# ME433.net
KiCad netlist of a schematic drawn in EAGLE
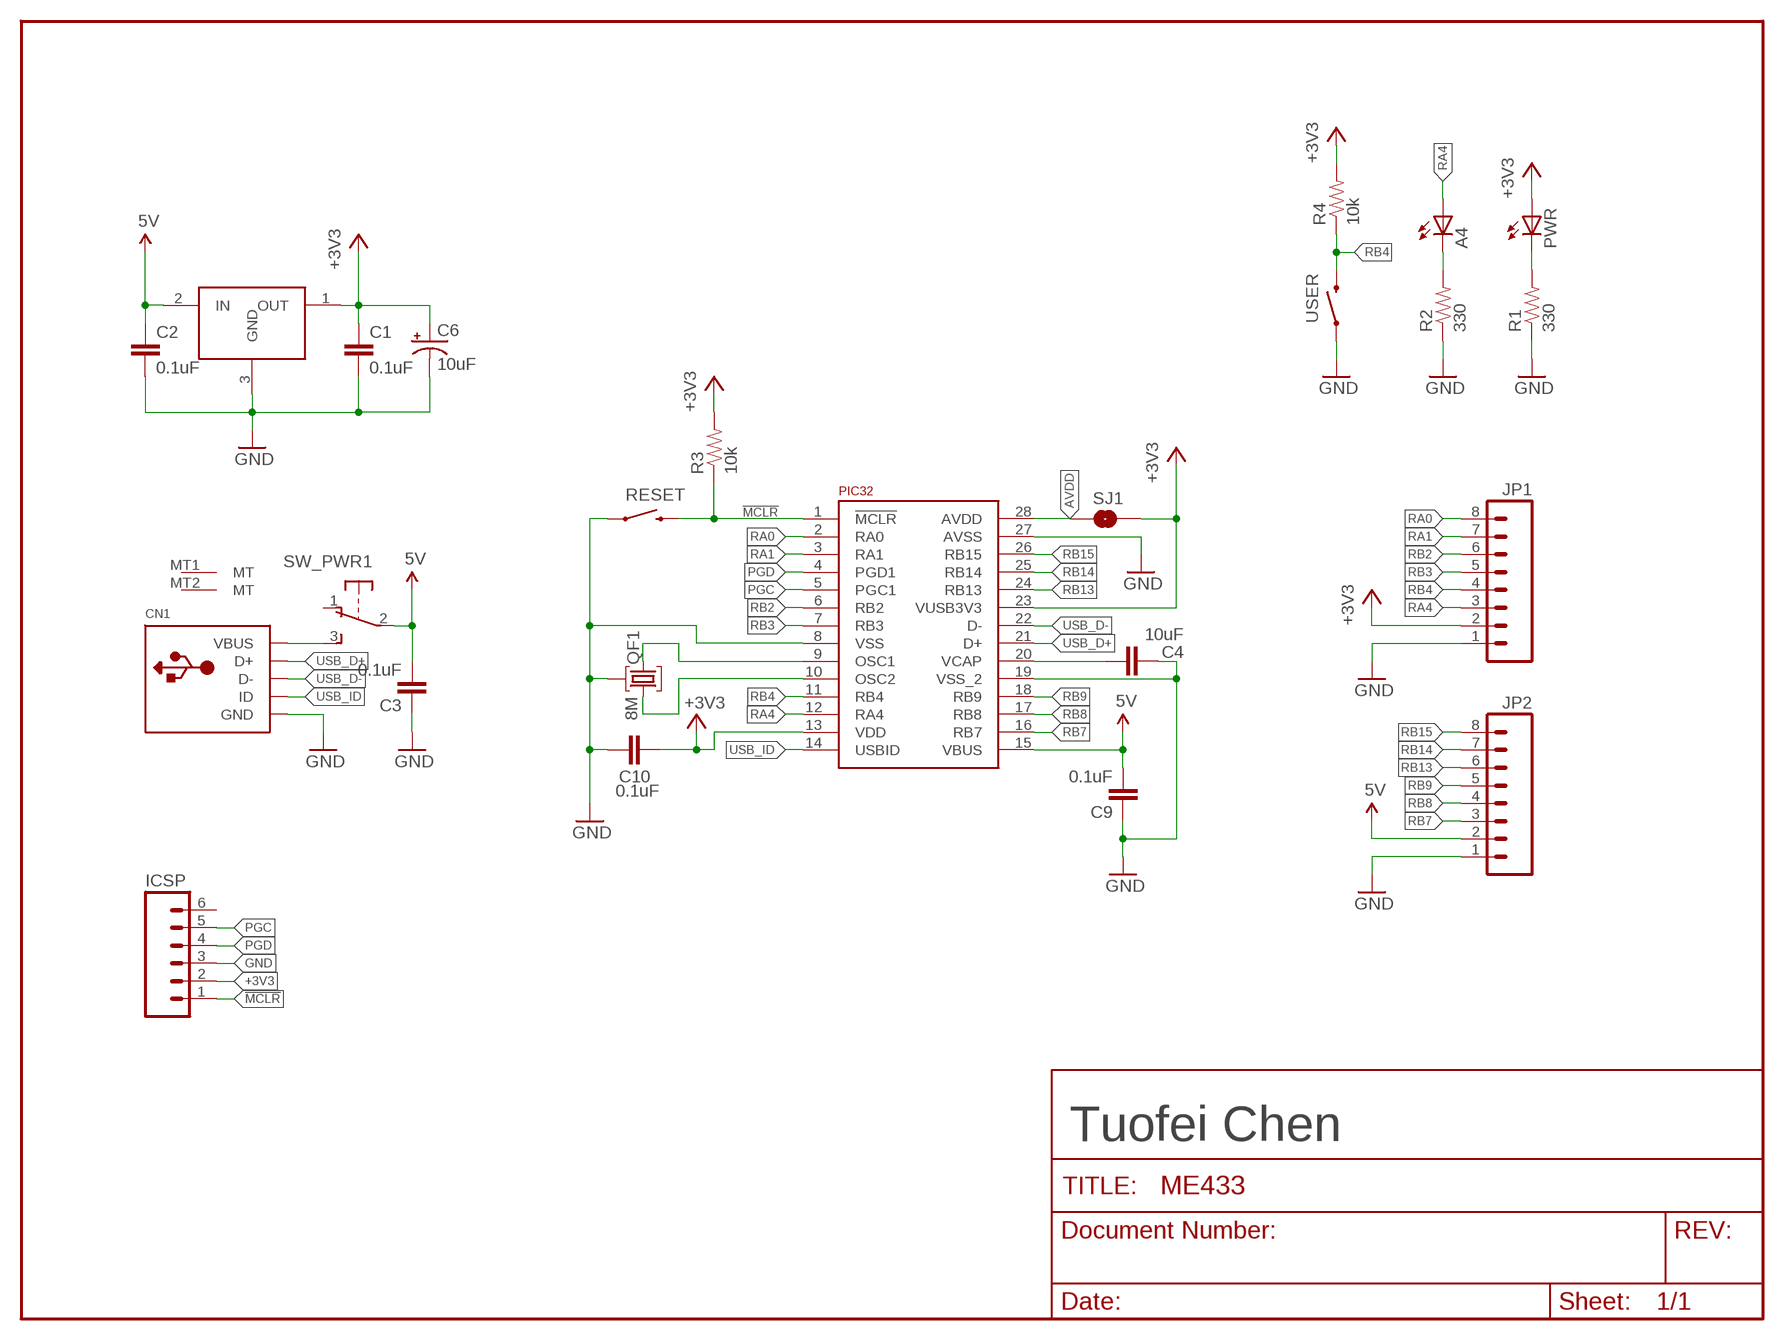
[diagram p0: schematic, sheet 1]

(export (version "E")
  (design (tool "Eeschema 10.0.6"))
  (components
    (comp (ref "3V3-REG")
      (value "3V3-REG-TO92")
      (footprint "eagle-import:TO-92")
      (libsource (lib "eagle-import") (part "3V3-REG-TO92"))
    )
    (comp (ref "A4")
      (value "LED3MM")
      (footprint "eagle-import:LED3MM")
      (libsource (lib "eagle-import") (part "LED3MM"))
    )
    (comp (ref "C1")
      (value "0.1uF")
      (footprint "eagle-import:CAP-PTH-SMALL")
      (libsource (lib "eagle-import") (part "CAPPTH"))
    )
    (comp (ref "C2")
      (value "0.1uF")
      (footprint "eagle-import:CAP-PTH-SMALL")
      (libsource (lib "eagle-import") (part "CAPPTH"))
    )
    (comp (ref "C3")
      (value "0.1uF")
      (footprint "eagle-import:CAP-PTH-SMALL")
      (libsource (lib "eagle-import") (part "CAPPTH"))
    )
    (comp (ref "C4")
      (value "10uF")
      (footprint "eagle-import:CAP-PTH-SMALL")
      (libsource (lib "eagle-import") (part "CAPPTH"))
    )
    (comp (ref "C6")
      (value "10uF")
      (footprint "eagle-import:CPOL-RADIAL-100UF-25V")
      (libsource (lib "eagle-import") (part "CAP_POLPTH1"))
    )
    (comp (ref "C9")
      (value "0.1uF")
      (footprint "eagle-import:CAP-PTH-SMALL")
      (libsource (lib "eagle-import") (part "CAPPTH"))
    )
    (comp (ref "C10")
      (value "0.1uF")
      (footprint "eagle-import:CAP-PTH-SMALL")
      (libsource (lib "eagle-import") (part "CAPPTH"))
    )
    (comp (ref "CN1")
      (value "USBMOLEX")
      (footprint "eagle-import:USB-MINIB-THM-MOLEX")
      (libsource (lib "eagle-import") (part "USBMOLEX"))
    )
    (comp (ref "ICSP")
      (value "M06LONGPADS")
      (footprint "eagle-import:1X06_LONGPADS")
      (libsource (lib "eagle-import") (part "M06LONGPADS"))
    )
    (comp (ref "JP1")
      (value "M08")
      (footprint "eagle-import:1X08")
      (libsource (lib "eagle-import") (part "M08"))
    )
    (comp (ref "JP2")
      (value "M08")
      (footprint "eagle-import:1X08")
      (libsource (lib "eagle-import") (part "M08"))
    )
    (comp (ref "PIC32")
      (value "PIC32MX250F128B-DIP")
      (footprint "eagle-import:DIP28")
      (libsource (lib "eagle-import") (part "PIC32MX250F128B-DIP"))
    )
    (comp (ref "PWR")
      (value "LED3MM")
      (footprint "eagle-import:LED3MM")
      (libsource (lib "eagle-import") (part "LED3MM"))
    )
    (comp (ref "QF1")
      (value "8M")
      (footprint "eagle-import:HC49U")
      (libsource (lib "eagle-import") (part "8M10AHC49T"))
    )
    (comp (ref "R1")
      (value "330")
      (footprint "eagle-import:AXIAL-0.3")
      (libsource (lib "eagle-import") (part "RESISTORAXIAL-0.3"))
    )
    (comp (ref "R2")
      (value "330")
      (footprint "eagle-import:AXIAL-0.3")
      (libsource (lib "eagle-import") (part "RESISTORAXIAL-0.3"))
    )
    (comp (ref "R3")
      (value "10k")
      (footprint "eagle-import:AXIAL-0.3")
      (libsource (lib "eagle-import") (part "RESISTORAXIAL-0.3"))
    )
    (comp (ref "R4")
      (value "10k")
      (footprint "eagle-import:AXIAL-0.3")
      (libsource (lib "eagle-import") (part "RESISTORAXIAL-0.3"))
    )
    (comp (ref "RESET")
      (value "PUSH_BUT")
      (footprint "eagle-import:1X02_LOCK_LONGPADS")
      (libsource (lib "eagle-import") (part "PUSH_BUT"))
    )
    (comp (ref "SJ1")
      (value "SOLDERJUMPERNC")
      (footprint "eagle-import:SJ_2S")
      (libsource (lib "eagle-import") (part "SOLDERJUMPERNC"))
    )
    (comp (ref "SW_PWR")
      (value "EG1213")
      (footprint "eagle-import:EG1213")
      (libsource (lib "eagle-import") (part "EG1213"))
    )
    (comp (ref "USER")
      (value "PUSH_BUT")
      (footprint "eagle-import:1X02_LOCK_LONGPADS")
      (libsource (lib "eagle-import") (part "PUSH_BUT"))
    )
  )
  (nets
    (net (code "1") (name "+3V3") (class "Default")
      (node (ref "3V3-REG") (pin "1") (pinfunction "OUT_1") (pintype "bidirectional"))
      (node (ref "C1") (pin "1") (pinfunction "1_1") (pintype "passive"))
      (node (ref "C10") (pin "2") (pinfunction "2_2") (pintype "passive"))
      (node (ref "C6") (pin "1") (pinfunction "+_1") (pintype "passive"))
      (node (ref "ICSP") (pin "2") (pinfunction "2_2") (pintype "passive"))
      (node (ref "JP1") (pin "2") (pinfunction "2_2") (pintype "passive"))
      (node (ref "PIC32") (pin "13") (pinfunction "VDD_13") (pintype "bidirectional"))
      (node (ref "PIC32") (pin "23") (pinfunction "VUSB3V3_23") (pintype "bidirectional"))
      (node (ref "PWR") (pin "A") (pinfunction "A_A") (pintype "passive"))
      (node (ref "R3") (pin "P$2") (pinfunction "2_P$2") (pintype "passive"))
      (node (ref "R4") (pin "P$2") (pinfunction "2_P$2") (pintype "passive"))
      (node (ref "SJ1") (pin "1") (pinfunction "1_1") (pintype "passive"))
    )
    (net (code "2") (name "/~{MCLR}") (class "Default")
      (node (ref "ICSP") (pin "1") (pinfunction "1_1") (pintype "passive"))
      (node (ref "PIC32") (pin "1") (pinfunction "~{MCLR}_1") (pintype "bidirectional"))
      (node (ref "R3") (pin "P$1") (pinfunction "1_P$1") (pintype "passive"))
      (node (ref "RESET") (pin "2") (pinfunction "2_2") (pintype "passive"))
    )
    (net (code "3") (name "5V") (class "Default")
      (node (ref "3V3-REG") (pin "2") (pinfunction "IN_2") (pintype "bidirectional"))
      (node (ref "C2") (pin "1") (pinfunction "1_1") (pintype "passive"))
      (node (ref "C3") (pin "2") (pinfunction "2_2") (pintype "passive"))
      (node (ref "C9") (pin "2") (pinfunction "2_2") (pintype "passive"))
      (node (ref "JP2") (pin "2") (pinfunction "2_2") (pintype "passive"))
      (node (ref "PIC32") (pin "15") (pinfunction "VBUS_15") (pintype "bidirectional"))
      (node (ref "SW_PWR") (pin "2") (pinfunction "P_2") (pintype "passive"))
    )
    (net (code "4") (name "AVDD") (class "Default")
      (node (ref "PIC32") (pin "28") (pinfunction "AVDD_28") (pintype "bidirectional"))
      (node (ref "SJ1") (pin "2") (pinfunction "2_2") (pintype "passive"))
    )
    (net (code "5") (name "GND") (class "Default")
      (node (ref "3V3-REG") (pin "3") (pinfunction "GND_3") (pintype "bidirectional"))
      (node (ref "C1") (pin "2") (pinfunction "2_2") (pintype "passive"))
      (node (ref "C10") (pin "1") (pinfunction "1_1") (pintype "passive"))
      (node (ref "C2") (pin "2") (pinfunction "2_2") (pintype "passive"))
      (node (ref "C3") (pin "1") (pinfunction "1_1") (pintype "passive"))
      (node (ref "C4") (pin "2") (pinfunction "2_2") (pintype "passive"))
      (node (ref "C6") (pin "2") (pinfunction "-_2") (pintype "passive"))
      (node (ref "C9") (pin "1") (pinfunction "1_1") (pintype "passive"))
      (node (ref "CN1") (pin "GND") (pinfunction "GND_GND") (pintype "power_in"))
      (node (ref "ICSP") (pin "3") (pinfunction "3_3") (pintype "passive"))
      (node (ref "JP1") (pin "1") (pinfunction "1_1") (pintype "passive"))
      (node (ref "JP2") (pin "1") (pinfunction "1_1") (pintype "passive"))
      (node (ref "PIC32") (pin "19") (pinfunction "VSS_2_19") (pintype "bidirectional"))
      (node (ref "PIC32") (pin "27") (pinfunction "AVSS_27") (pintype "bidirectional"))
      (node (ref "PIC32") (pin "8") (pinfunction "VSS_8") (pintype "bidirectional"))
      (node (ref "QF1") (pin "2") (pinfunction "2_2") (pintype "passive"))
      (node (ref "R1") (pin "P$1") (pinfunction "1_P$1") (pintype "passive"))
      (node (ref "R2") (pin "P$1") (pinfunction "1_P$1") (pintype "passive"))
      (node (ref "RESET") (pin "1") (pinfunction "1_1") (pintype "passive"))
      (node (ref "USER") (pin "1") (pinfunction "1_1") (pintype "passive"))
    )
    (net (code "6") (name "Net-(A4-C)") (class "Default")
      (node (ref "A4") (pin "K") (pinfunction "C_K") (pintype "passive"))
      (node (ref "R2") (pin "P$2") (pinfunction "2_P$2") (pintype "passive"))
    )
    (net (code "7") (name "Net-(PIC32-OSC1)") (class "Default")
      (node (ref "PIC32") (pin "9") (pinfunction "OSC1_9") (pintype "bidirectional"))
      (node (ref "QF1") (pin "1") (pinfunction "1_1") (pintype "passive"))
    )
    (net (code "8") (name "Net-(PIC32-OSC2)") (class "Default")
      (node (ref "PIC32") (pin "10") (pinfunction "OSC2_10") (pintype "bidirectional"))
      (node (ref "QF1") (pin "3") (pinfunction "3_3") (pintype "passive"))
    )
    (net (code "9") (name "Net-(PIC32-VCAP)") (class "Default")
      (node (ref "C4") (pin "1") (pinfunction "1_1") (pintype "passive"))
      (node (ref "PIC32") (pin "20") (pinfunction "VCAP_20") (pintype "bidirectional"))
    )
    (net (code "10") (name "Net-(PWR-C)") (class "Default")
      (node (ref "PWR") (pin "K") (pinfunction "C_K") (pintype "passive"))
      (node (ref "R1") (pin "P$2") (pinfunction "2_P$2") (pintype "passive"))
    )
    (net (code "11") (name "Net-(SW_PWRA-S)") (class "Default")
      (node (ref "CN1") (pin "VBUS") (pinfunction "VBUS_VBUS") (pintype "power_in"))
      (node (ref "SW_PWR") (pin "3") (pinfunction "S_3") (pintype "passive"))
    )
    (net (code "12") (name "PGC") (class "Default")
      (node (ref "ICSP") (pin "5") (pinfunction "5_5") (pintype "passive"))
      (node (ref "PIC32") (pin "5") (pinfunction "PGC1_5") (pintype "bidirectional"))
    )
    (net (code "13") (name "PGD") (class "Default")
      (node (ref "ICSP") (pin "4") (pinfunction "4_4") (pintype "passive"))
      (node (ref "PIC32") (pin "4") (pinfunction "PGD1_4") (pintype "bidirectional"))
    )
    (net (code "14") (name "RA0") (class "Default")
      (node (ref "JP1") (pin "8") (pinfunction "8_8") (pintype "passive"))
      (node (ref "PIC32") (pin "2") (pinfunction "RA0_2") (pintype "bidirectional"))
    )
    (net (code "15") (name "RA1") (class "Default")
      (node (ref "JP1") (pin "7") (pinfunction "7_7") (pintype "passive"))
      (node (ref "PIC32") (pin "3") (pinfunction "RA1_3") (pintype "bidirectional"))
    )
    (net (code "16") (name "RA4") (class "Default")
      (node (ref "A4") (pin "A") (pinfunction "A_A") (pintype "passive"))
      (node (ref "JP1") (pin "3") (pinfunction "3_3") (pintype "passive"))
      (node (ref "PIC32") (pin "12") (pinfunction "RA4_12") (pintype "bidirectional"))
    )
    (net (code "17") (name "RB2") (class "Default")
      (node (ref "JP1") (pin "6") (pinfunction "6_6") (pintype "passive"))
      (node (ref "PIC32") (pin "6") (pinfunction "RB2_6") (pintype "bidirectional"))
    )
    (net (code "18") (name "RB3") (class "Default")
      (node (ref "JP1") (pin "5") (pinfunction "5_5") (pintype "passive"))
      (node (ref "PIC32") (pin "7") (pinfunction "RB3_7") (pintype "bidirectional"))
    )
    (net (code "19") (name "RB4") (class "Default")
      (node (ref "JP1") (pin "4") (pinfunction "4_4") (pintype "passive"))
      (node (ref "PIC32") (pin "11") (pinfunction "RB4_11") (pintype "bidirectional"))
      (node (ref "R4") (pin "P$1") (pinfunction "1_P$1") (pintype "passive"))
      (node (ref "USER") (pin "2") (pinfunction "2_2") (pintype "passive"))
    )
    (net (code "20") (name "RB7") (class "Default")
      (node (ref "JP2") (pin "3") (pinfunction "3_3") (pintype "passive"))
      (node (ref "PIC32") (pin "16") (pinfunction "RB7_16") (pintype "bidirectional"))
    )
    (net (code "21") (name "RB8") (class "Default")
      (node (ref "JP2") (pin "4") (pinfunction "4_4") (pintype "passive"))
      (node (ref "PIC32") (pin "17") (pinfunction "RB8_17") (pintype "bidirectional"))
    )
    (net (code "22") (name "RB9") (class "Default")
      (node (ref "JP2") (pin "5") (pinfunction "5_5") (pintype "passive"))
      (node (ref "PIC32") (pin "18") (pinfunction "RB9_18") (pintype "bidirectional"))
    )
    (net (code "23") (name "RB13") (class "Default")
      (node (ref "JP2") (pin "6") (pinfunction "6_6") (pintype "passive"))
      (node (ref "PIC32") (pin "24") (pinfunction "RB13_24") (pintype "bidirectional"))
    )
    (net (code "24") (name "RB14") (class "Default")
      (node (ref "JP2") (pin "7") (pinfunction "7_7") (pintype "passive"))
      (node (ref "PIC32") (pin "25") (pinfunction "RB14_25") (pintype "bidirectional"))
    )
    (net (code "25") (name "RB15") (class "Default")
      (node (ref "JP2") (pin "8") (pinfunction "8_8") (pintype "passive"))
      (node (ref "PIC32") (pin "26") (pinfunction "RB15_26") (pintype "bidirectional"))
    )
    (net (code "26") (name "USB_D+") (class "Default")
      (node (ref "CN1") (pin "D+") (pinfunction "D+_D+") (pintype "bidirectional"))
      (node (ref "PIC32") (pin "21") (pinfunction "D+_21") (pintype "bidirectional"))
    )
    (net (code "27") (name "USB_D-") (class "Default")
      (node (ref "CN1") (pin "D-") (pinfunction "D-_D-") (pintype "bidirectional"))
      (node (ref "PIC32") (pin "22") (pinfunction "D-_22") (pintype "bidirectional"))
    )
    (net (code "28") (name "USB_ID") (class "Default")
      (node (ref "CN1") (pin "ID") (pinfunction "ID_ID") (pintype "bidirectional"))
      (node (ref "PIC32") (pin "14") (pinfunction "USBID_14") (pintype "bidirectional"))
    )
    (net (code "29") (name "unconnected-(ICSP-Pad6)") (class "Default")
      (node (ref "ICSP") (pin "6") (pinfunction "6_6") (pintype "passive"))
    )
    (net (code "30") (name "unconnected-(SW_PWRA-O-Pad1)") (class "Default")
      (node (ref "SW_PWR") (pin "1") (pinfunction "O_1") (pintype "passive"))
    )
    (net (code "31") (name "unconnected-(SW_PWRB-MT-PadMT1)") (class "Default")
      (node (ref "SW_PWR") (pin "MT1") (pinfunction "MT_MT1") (pintype "passive"))
    )
    (net (code "32") (name "unconnected-(SW_PWRC-MT-PadMT2)") (class "Default")
      (node (ref "SW_PWR") (pin "MT2") (pinfunction "MT_MT2") (pintype "passive"))
    )
  )
)
